# arduino_uno.net
KiCad netlist of a schematic drawn in EAGLE
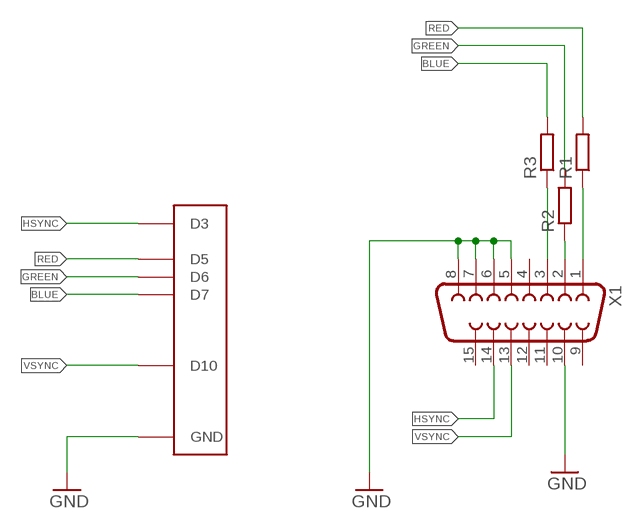
[diagram p0: schematic, sheet 1]

(export (version "E")
  (design (tool "Eeschema 10.0.6"))
  (components
    (comp (ref "R1")
      (value "R-EU_0207/10")
      (footprint "eagle-import:0207_10")
      (libsource (lib "eagle-import") (part "R-EU_0207/10"))
    )
    (comp (ref "R2")
      (value "R-EU_0207/10")
      (footprint "eagle-import:0207_10")
      (libsource (lib "eagle-import") (part "R-EU_0207/10"))
    )
    (comp (ref "R3")
      (value "R-EU_0207/10")
      (footprint "eagle-import:0207_10")
      (libsource (lib "eagle-import") (part "R-EU_0207/10"))
    )
    (comp (ref "U$1")
      (value "ARDUINOUNO")
      (footprint "eagle-import:ARDUINO")
      (libsource (lib "eagle-import") (part "ARDUINOUNO"))
    )
    (comp (ref "X1")
      (value "F15HDV")
      (footprint "eagle-import:HDF15V")
      (libsource (lib "eagle-import") (part "F15HDV"))
    )
  )
  (nets
    (net (code "1") (name "BLUE") (class "Default")
      (node (ref "R3") (pin "2") (pinfunction "2_2") (pintype "passive"))
      (node (ref "U$1") (pin "D7") (pinfunction "D7_D7") (pintype "bidirectional"))
    )
    (net (code "2") (name "GND") (class "Default")
      (node (ref "U$1") (pin "GND") (pinfunction "GND_GND") (pintype "power_in"))
      (node (ref "X1") (pin "10") (pinfunction "10_10") (pintype "passive"))
      (node (ref "X1") (pin "5") (pinfunction "5_5") (pintype "passive"))
      (node (ref "X1") (pin "6") (pinfunction "6_6") (pintype "passive"))
      (node (ref "X1") (pin "7") (pinfunction "7_7") (pintype "passive"))
      (node (ref "X1") (pin "8") (pinfunction "8_8") (pintype "passive"))
    )
    (net (code "3") (name "GREEN") (class "Default")
      (node (ref "R2") (pin "2") (pinfunction "2_2") (pintype "passive"))
      (node (ref "U$1") (pin "D6") (pinfunction "D6_D6") (pintype "bidirectional"))
    )
    (net (code "4") (name "HSYNC") (class "Default")
      (node (ref "U$1") (pin "D3") (pinfunction "D3_D3") (pintype "bidirectional"))
      (node (ref "X1") (pin "14") (pinfunction "14_14") (pintype "passive"))
    )
    (net (code "5") (name "Net-(R1-Pad1)") (class "Default")
      (node (ref "R1") (pin "1") (pinfunction "1_1") (pintype "passive"))
      (node (ref "X1") (pin "1") (pinfunction "1_1") (pintype "passive"))
    )
    (net (code "6") (name "Net-(R2-Pad1)") (class "Default")
      (node (ref "R2") (pin "1") (pinfunction "1_1") (pintype "passive"))
      (node (ref "X1") (pin "2") (pinfunction "2_2") (pintype "passive"))
    )
    (net (code "7") (name "Net-(R3-Pad1)") (class "Default")
      (node (ref "R3") (pin "1") (pinfunction "1_1") (pintype "passive"))
      (node (ref "X1") (pin "3") (pinfunction "3_3") (pintype "passive"))
    )
    (net (code "8") (name "RED") (class "Default")
      (node (ref "R1") (pin "2") (pinfunction "2_2") (pintype "passive"))
      (node (ref "U$1") (pin "D5") (pinfunction "D5_D5") (pintype "bidirectional"))
    )
    (net (code "9") (name "VSYNC") (class "Default")
      (node (ref "U$1") (pin "D10") (pinfunction "D10_D10") (pintype "bidirectional"))
      (node (ref "X1") (pin "13") (pinfunction "13_13") (pintype "passive"))
    )
    (net (code "10") (name "unconnected-(X1-Pad4)") (class "Default")
      (node (ref "X1") (pin "4") (pinfunction "4_4") (pintype "passive"))
    )
    (net (code "11") (name "unconnected-(X1-Pad9)") (class "Default")
      (node (ref "X1") (pin "9") (pinfunction "9_9") (pintype "passive"))
    )
    (net (code "12") (name "unconnected-(X1-Pad11)") (class "Default")
      (node (ref "X1") (pin "11") (pinfunction "11_11") (pintype "passive"))
    )
    (net (code "13") (name "unconnected-(X1-Pad12)") (class "Default")
      (node (ref "X1") (pin "12") (pinfunction "12_12") (pintype "passive"))
    )
    (net (code "14") (name "unconnected-(X1-Pad15)") (class "Default")
      (node (ref "X1") (pin "15") (pinfunction "15_15") (pintype "passive"))
    )
  )
)
